# 8-connector.net
KiCad netlist of a schematic drawn in Altium Designer
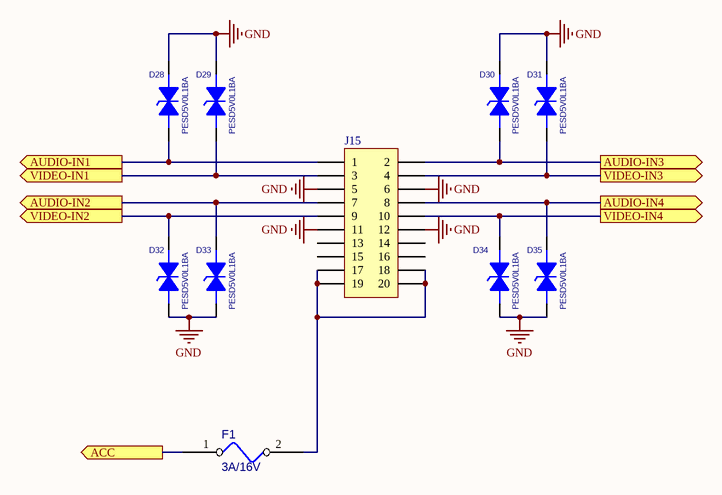
[diagram p0: 8-connector.SchDoc]

(export (version "E")
  (design (tool "Eeschema 10.0.6"))
  (components
    (comp (ref "D28") (value "PESD5V0L1BA") (libsource (lib "*") (part "PESD")))
    (comp (ref "D29") (value "PESD5V0L1BA") (libsource (lib "*") (part "PESD")))
    (comp (ref "D30") (value "PESD5V0L1BA") (libsource (lib "*") (part "PESD")))
    (comp (ref "D31") (value "PESD5V0L1BA") (libsource (lib "*") (part "PESD")))
    (comp (ref "D32") (value "PESD5V0L1BA") (libsource (lib "*") (part "PESD")))
    (comp (ref "D33") (value "PESD5V0L1BA") (libsource (lib "*") (part "PESD")))
    (comp (ref "D34") (value "PESD5V0L1BA") (libsource (lib "*") (part "PESD")))
    (comp (ref "D35") (value "PESD5V0L1BA") (libsource (lib "*") (part "PESD")))
    (comp (ref "F1") (value "3A/16V") (libsource (lib "*") (part "2A_32VDC_0467-002")))
    (comp (ref "J15")
      (value "Header 10X2")
      (footprint "CONN2X10")
      (description "Header, 10-Pin, Dual row")
      (fields (field (name "PUBLISHER") "Altium Limited"))
      (libsource (lib "Miscellaneous Connectors") (part "Header 10X2"))
    )
  )
  (nets
    (net (code "1") (name "/ACC") (class "Default")
      (node (ref "F1") (pin "1") (pinfunction "1_1") (pintype "passive"))
    )
    (net (code "2") (name "/AUDIO-IN1") (class "Default")
      (node (ref "D28") (pin "1") (pinfunction "1_1") (pintype "passive"))
      (node (ref "J15") (pin "1") (pinfunction "1_1") (pintype "passive"))
    )
    (net (code "3") (name "/AUDIO-IN2") (class "Default")
      (node (ref "D33") (pin "2") (pinfunction "2_2") (pintype "passive"))
      (node (ref "J15") (pin "7") (pinfunction "7_7") (pintype "passive"))
    )
    (net (code "4") (name "/AUDIO-IN3") (class "Default")
      (node (ref "D30") (pin "1") (pinfunction "1_1") (pintype "passive"))
      (node (ref "J15") (pin "2") (pinfunction "2_2") (pintype "passive"))
    )
    (net (code "5") (name "/AUDIO-IN4") (class "Default")
      (node (ref "D35") (pin "2") (pinfunction "2_2") (pintype "passive"))
      (node (ref "J15") (pin "8") (pinfunction "8_8") (pintype "passive"))
    )
    (net (code "6") (name "/VIDEO-IN1") (class "Default")
      (node (ref "D29") (pin "1") (pinfunction "1_1") (pintype "passive"))
      (node (ref "J15") (pin "3") (pinfunction "3_3") (pintype "passive"))
    )
    (net (code "7") (name "/VIDEO-IN2") (class "Default")
      (node (ref "D32") (pin "2") (pinfunction "2_2") (pintype "passive"))
      (node (ref "J15") (pin "9") (pinfunction "9_9") (pintype "passive"))
    )
    (net (code "8") (name "/VIDEO-IN3") (class "Default")
      (node (ref "D31") (pin "1") (pinfunction "1_1") (pintype "passive"))
      (node (ref "J15") (pin "4") (pinfunction "4_4") (pintype "passive"))
    )
    (net (code "9") (name "/VIDEO-IN4") (class "Default")
      (node (ref "D34") (pin "2") (pinfunction "2_2") (pintype "passive"))
      (node (ref "J15") (pin "10") (pinfunction "10_10") (pintype "passive"))
    )
    (net (code "10") (name "GND") (class "Default")
      (node (ref "D28") (pin "2") (pinfunction "2_2") (pintype "passive"))
      (node (ref "D29") (pin "2") (pinfunction "2_2") (pintype "passive"))
      (node (ref "D30") (pin "2") (pinfunction "2_2") (pintype "passive"))
      (node (ref "D31") (pin "2") (pinfunction "2_2") (pintype "passive"))
      (node (ref "D32") (pin "1") (pinfunction "1_1") (pintype "passive"))
      (node (ref "D33") (pin "1") (pinfunction "1_1") (pintype "passive"))
      (node (ref "D34") (pin "1") (pinfunction "1_1") (pintype "passive"))
      (node (ref "D35") (pin "1") (pinfunction "1_1") (pintype "passive"))
      (node (ref "J15") (pin "11") (pinfunction "11_11") (pintype "passive"))
      (node (ref "J15") (pin "12") (pinfunction "12_12") (pintype "passive"))
      (node (ref "J15") (pin "5") (pinfunction "5_5") (pintype "passive"))
      (node (ref "J15") (pin "6") (pinfunction "6_6") (pintype "passive"))
    )
    (net (code "11") (name "Net-(F1-Pad2)") (class "Default")
      (node (ref "F1") (pin "2") (pinfunction "2_2") (pintype "passive"))
      (node (ref "J15") (pin "17") (pinfunction "17_17") (pintype "passive"))
      (node (ref "J15") (pin "18") (pinfunction "18_18") (pintype "passive"))
      (node (ref "J15") (pin "19") (pinfunction "19_19") (pintype "passive"))
      (node (ref "J15") (pin "20") (pinfunction "20_20") (pintype "passive"))
    )
    (net (code "12") (name "unconnected-(J15-Pad13)") (class "Default")
      (node (ref "J15") (pin "13") (pinfunction "13_13") (pintype "passive"))
    )
    (net (code "13") (name "unconnected-(J15-Pad14)") (class "Default")
      (node (ref "J15") (pin "14") (pinfunction "14_14") (pintype "passive"))
    )
    (net (code "14") (name "unconnected-(J15-Pad15)") (class "Default")
      (node (ref "J15") (pin "15") (pinfunction "15_15") (pintype "passive"))
    )
    (net (code "15") (name "unconnected-(J15-Pad16)") (class "Default")
      (node (ref "J15") (pin "16") (pinfunction "16_16") (pintype "passive"))
    )
  )
)
